# PollutagNode2_rev4_2026-10-08.net
KiCad netlist of a schematic drawn in EasyEDA Pro
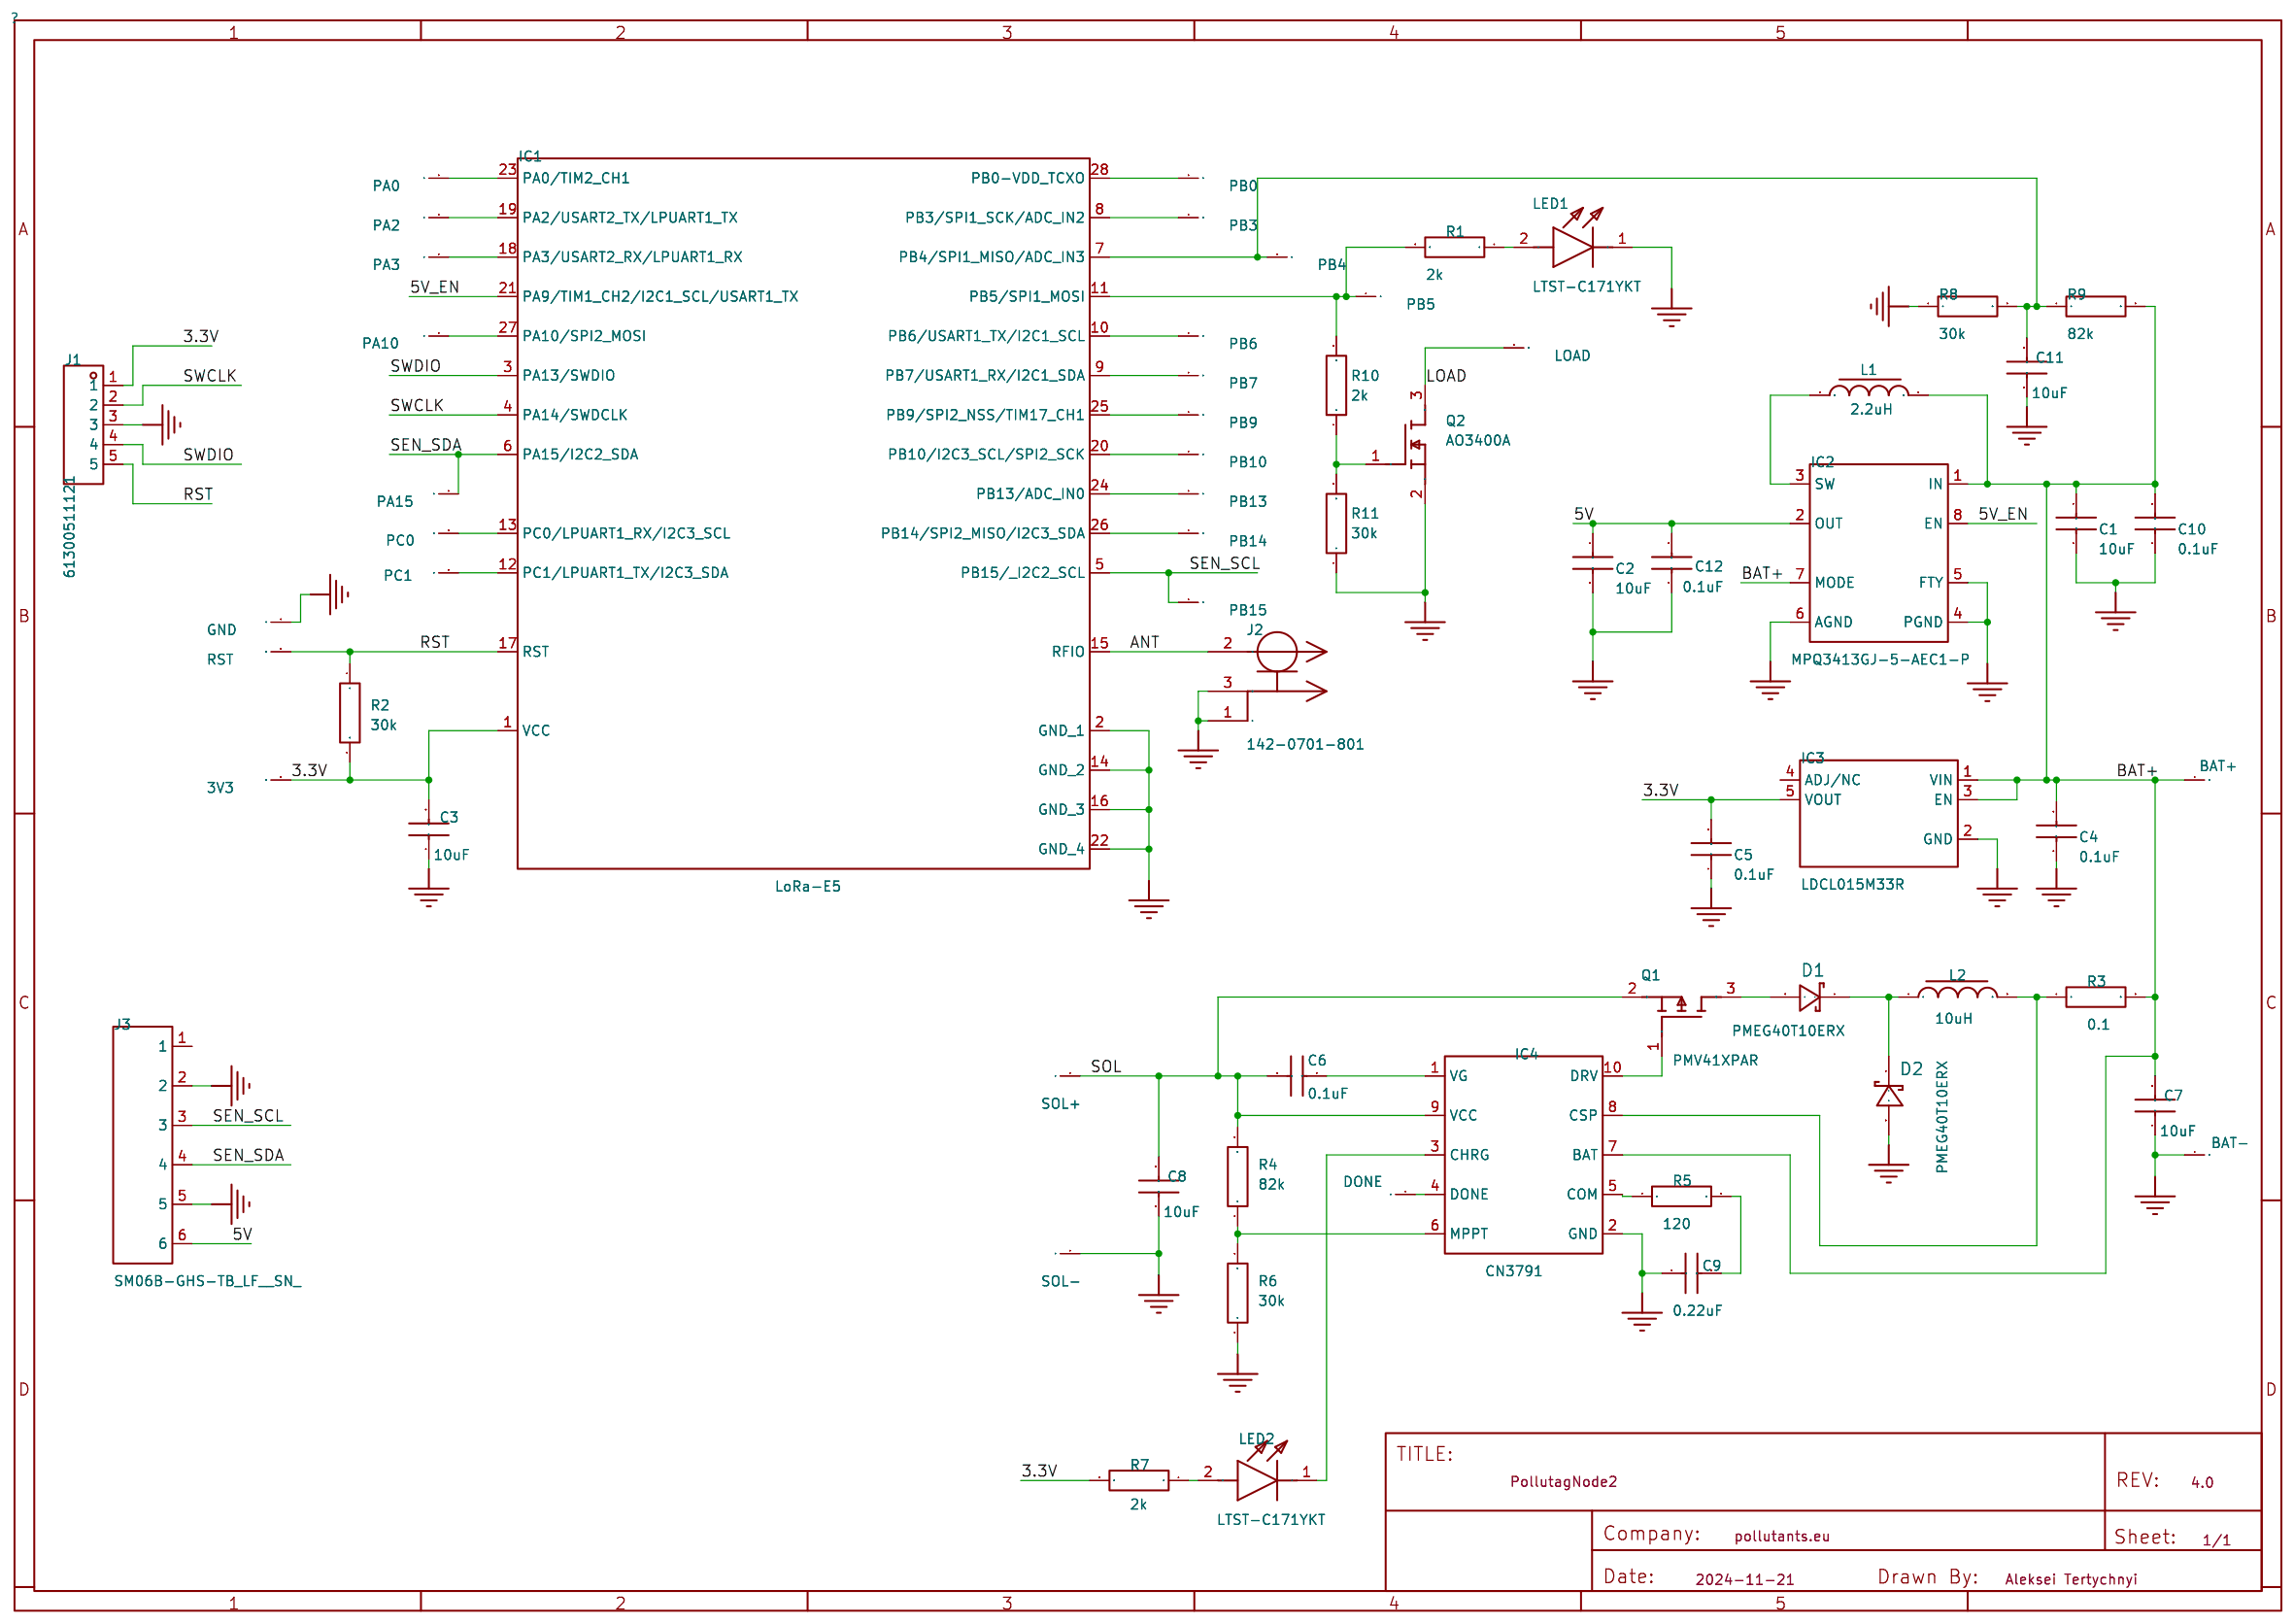
[diagram p0: schematic sheet]

(export (version "E")
  (design (tool "Eeschema 10.0.6"))
  (components
    (comp (ref "3V3")
      (value "S1751-46R")
      (fields (field (name "Manufacturer") "Harwin"))
      (libsource (lib "") (part "S1751-46R_1"))
    )
    (comp (ref "BAT+")
      (value "S1751-46R")
      (fields (field (name "Manufacturer") "Harwin"))
      (libsource (lib "easyedapro") (part "S1751-46R"))
    )
    (comp (ref "BAT-")
      (value "S1751-46R")
      (fields (field (name "Manufacturer") "Harwin"))
      (libsource (lib "easyedapro") (part "S1751-46R"))
    )
    (comp (ref "C1")
      (value "10uF")
      (fields
        (field (name "Manufacturer Part") "GRM188R61C106KALD")
        (field (name "Manufacturer") "Murata Electronics")
      )
      (libsource (lib "easyedapro") (part "10uF"))
    )
    (comp (ref "C2")
      (value "10uF")
      (fields
        (field (name "Manufacturer Part") "GRM188R61C106KALD")
        (field (name "Manufacturer") "Murata Electronics")
      )
      (libsource (lib "easyedapro") (part "10uF"))
    )
    (comp (ref "C3")
      (value "10uF")
      (fields
        (field (name "Manufacturer Part") "GRM188R61C106KALD")
        (field (name "Manufacturer") "Murata Electronics")
      )
      (libsource (lib "easyedapro") (part "10uF"))
    )
    (comp (ref "C4")
      (value "0.1uF")
      (fields (field (name "Manufacturer Part") "06035C104KAT2A") (field (name "Manufacturer") "AVX"))
      (libsource (lib "easyedapro") (part "0.1uF"))
    )
    (comp (ref "C5")
      (value "0.1uF")
      (fields (field (name "Manufacturer Part") "06035C104KAT2A") (field (name "Manufacturer") "AVX"))
      (libsource (lib "easyedapro") (part "0.1uF"))
    )
    (comp (ref "C6")
      (value "0.1uF")
      (fields (field (name "Manufacturer Part") "06035C104KAT2A") (field (name "Manufacturer") "AVX"))
      (libsource (lib "easyedapro") (part "0.1uF"))
    )
    (comp (ref "C7")
      (value "10uF")
      (fields
        (field (name "Manufacturer Part") "GRM188R61C106KALD")
        (field (name "Manufacturer") "Murata Electronics")
      )
      (libsource (lib "easyedapro") (part "10uF"))
    )
    (comp (ref "C8")
      (value "10uF")
      (fields
        (field (name "Manufacturer Part") "GRM188R61C106KALD")
        (field (name "Manufacturer") "Murata Electronics")
      )
      (libsource (lib "easyedapro") (part "10uF"))
    )
    (comp (ref "C9")
      (value "0.22uF")
      (fields (field (name "Manufacturer Part") "AC0603X7R9BB224") (field (name "Manufacturer") "KEMET"))
      (libsource (lib "easyedapro") (part "0.22uF"))
    )
    (comp (ref "C10")
      (value "0.1uF")
      (fields (field (name "Manufacturer Part") "06035C104KAT2A") (field (name "Manufacturer") "AVX"))
      (libsource (lib "easyedapro") (part "0.1uF"))
    )
    (comp (ref "C11")
      (value "10uF")
      (fields
        (field (name "Manufacturer Part") "GRM188R61C106KALD")
        (field (name "Manufacturer") "Murata Electronics")
      )
      (libsource (lib "easyedapro") (part "10uF"))
    )
    (comp (ref "C12")
      (value "0.1uF")
      (fields (field (name "Manufacturer Part") "06035C104KAT2A") (field (name "Manufacturer") "AVX"))
      (libsource (lib "easyedapro") (part "0.1uF"))
    )
    (comp (ref "D1")
      (value "PMEG40T10ERX")
      (footprint "easyedapro:SOD-123_L2.6-W1.7-LS3.5-RD")
      (fields (field (name "Manufacturer") "Nexperia(安世)"))
      (libsource (lib "easyedapro") (part "PMEG40T10ERX"))
    )
    (comp (ref "D2")
      (value "PMEG40T10ERX")
      (footprint "easyedapro:SOD-123_L2.6-W1.7-LS3.5-RD")
      (fields (field (name "Manufacturer") "Nexperia(安世)"))
      (libsource (lib "easyedapro") (part "PMEG40T10ERX"))
    )
    (comp (ref "DONE")
      (value "S1751-46R")
      (fields (field (name "Manufacturer") "Harwin"))
      (libsource (lib "") (part "S1751-46R_1"))
    )
    (comp (ref "GND")
      (value "S1751-46R")
      (fields (field (name "Manufacturer") "Harwin"))
      (libsource (lib "") (part "S1751-46R_1"))
    )
    (comp (ref "IC1")
      (value "LoRa-E5")
      (fields (field (name "Manufacturer Part") "317990687") (field (name "Manufacturer") "SEEED STUDIO"))
      (libsource (lib "easyedapro") (part "LoRa-E5"))
    )
    (comp (ref "IC2")
      (value "MPQ3413GJ-5-AEC1-P")
      (fields (field (name "Manufacturer") "Monolithic Power Systems (MPS)"))
      (libsource (lib "easyedapro") (part "MPQ3413GJ-5-AEC1-P"))
    )
    (comp (ref "IC3")
      (value "LDCL015M33R")
      (fields (field (name "Manufacturer") "STMicroelectronics"))
      (libsource (lib "easyedapro") (part "LDCL015M33R"))
    )
    (comp (ref "IC4")
      (value "CN3791")
      (fields (field (name "Manufacturer") "Consonance"))
      (libsource (lib "easyedapro") (part "CN3791"))
    )
    (comp (ref "J1")
      (value "61300511121")
      (footprint "easyedapro:HDR-TH_5P-P2.54-V-M")
      (fields (field (name "Manufacturer") "Wurth(伍尔特)"))
      (libsource (lib "easyedapro") (part "61300511121"))
    )
    (comp (ref "J2")
      (value "142-0701-801")
      (fields (field (name "Manufacturer") "Cinch Connectivity Solutions"))
      (libsource (lib "easyedapro") (part "142-0701-801"))
    )
    (comp (ref "J3")
      (value "SM06B-GHS-TB_LF__SN_")
      (fields
        (field (name "Manufacturer Part") "SM06B-GHS-TB(LF)(SN)")
        (field (name "Manufacturer") "JST (JAPAN SOLDERLESS TERMINALS)")
      )
      (libsource (lib "easyedapro") (part "SM06B-GHS-TB_LF__SN_"))
    )
    (comp (ref "L1")
      (value "2.2uH")
      (fields (field (name "Manufacturer Part") "SRN3015-2R2M") (field (name "Manufacturer") "Bourns"))
      (libsource (lib "easyedapro") (part "2.2uH"))
    )
    (comp (ref "L2")
      (value "10uH")
      (fields (field (name "Manufacturer Part") "SRN3015BTA-100M") (field (name "Manufacturer") "Bourns"))
      (libsource (lib "easyedapro") (part "10uH"))
    )
    (comp (ref "LED1")
      (value "LTST-C171YKT")
      (fields (field (name "Manufacturer") "Lite-On"))
      (libsource (lib "easyedapro") (part "LTST-C171YKT"))
    )
    (comp (ref "LED2")
      (value "LTST-C171YKT")
      (fields (field (name "Manufacturer") "Lite-On"))
      (libsource (lib "easyedapro") (part "LTST-C171YKT"))
    )
    (comp (ref "LOAD")
      (value "S1751-46R")
      (fields (field (name "Manufacturer") "Harwin"))
      (libsource (lib "easyedapro") (part "S1751-46R"))
    )
    (comp (ref "PA0")
      (value "S1751-46R")
      (fields (field (name "Manufacturer") "Harwin"))
      (libsource (lib "") (part "S1751-46R_1"))
    )
    (comp (ref "PA2")
      (value "S1751-46R")
      (fields (field (name "Manufacturer") "Harwin"))
      (libsource (lib "") (part "S1751-46R_1"))
    )
    (comp (ref "PA3")
      (value "S1751-46R")
      (fields (field (name "Manufacturer") "Harwin"))
      (libsource (lib "") (part "S1751-46R_1"))
    )
    (comp (ref "PA10")
      (value "S1751-46R")
      (fields (field (name "Manufacturer") "Harwin"))
      (libsource (lib "") (part "S1751-46R_1"))
    )
    (comp (ref "PA15")
      (value "S1751-46R")
      (fields (field (name "Manufacturer") "Harwin"))
      (libsource (lib "") (part "S1751-46R_1"))
    )
    (comp (ref "PB0")
      (value "S1751-46R")
      (fields (field (name "Manufacturer") "Harwin"))
      (libsource (lib "easyedapro") (part "S1751-46R"))
    )
    (comp (ref "PB3")
      (value "S1751-46R")
      (fields (field (name "Manufacturer") "Harwin"))
      (libsource (lib "easyedapro") (part "S1751-46R"))
    )
    (comp (ref "PB4")
      (value "S1751-46R")
      (fields (field (name "Manufacturer") "Harwin"))
      (libsource (lib "easyedapro") (part "S1751-46R"))
    )
    (comp (ref "PB5")
      (value "S1751-46R")
      (fields (field (name "Manufacturer") "Harwin"))
      (libsource (lib "easyedapro") (part "S1751-46R"))
    )
    (comp (ref "PB6")
      (value "S1751-46R")
      (fields (field (name "Manufacturer") "Harwin"))
      (libsource (lib "easyedapro") (part "S1751-46R"))
    )
    (comp (ref "PB7")
      (value "S1751-46R")
      (fields (field (name "Manufacturer") "Harwin"))
      (libsource (lib "easyedapro") (part "S1751-46R"))
    )
    (comp (ref "PB9")
      (value "S1751-46R")
      (fields (field (name "Manufacturer") "Harwin"))
      (libsource (lib "easyedapro") (part "S1751-46R"))
    )
    (comp (ref "PB10")
      (value "S1751-46R")
      (fields (field (name "Manufacturer") "Harwin"))
      (libsource (lib "easyedapro") (part "S1751-46R"))
    )
    (comp (ref "PB13")
      (value "S1751-46R")
      (fields (field (name "Manufacturer") "Harwin"))
      (libsource (lib "easyedapro") (part "S1751-46R"))
    )
    (comp (ref "PB14")
      (value "S1751-46R")
      (fields (field (name "Manufacturer") "Harwin"))
      (libsource (lib "easyedapro") (part "S1751-46R"))
    )
    (comp (ref "PB15")
      (value "S1751-46R")
      (fields (field (name "Manufacturer") "Harwin"))
      (libsource (lib "easyedapro") (part "S1751-46R"))
    )
    (comp (ref "PC0")
      (value "S1751-46R")
      (fields (field (name "Manufacturer") "Harwin"))
      (libsource (lib "") (part "S1751-46R_1"))
    )
    (comp (ref "PC1")
      (value "S1751-46R")
      (fields (field (name "Manufacturer") "Harwin"))
      (libsource (lib "") (part "S1751-46R_1"))
    )
    (comp (ref "Q1")
      (value "PMV41XPAR")
      (fields (field (name "Manufacturer") "Nexperia"))
      (libsource (lib "easyedapro") (part "PMV41XPAR"))
    )
    (comp (ref "Q2")
      (value "AO3400A")
      (fields (field (name "Manufacturer") "Alpha & Omega Semiconductors"))
      (libsource (lib "easyedapro") (part "AO3400A"))
    )
    (comp (ref "R1")
      (value "2k")
      (fields (field (name "Manufacturer Part") "RC0603FR-072KL") (field (name "Manufacturer") "Yageo"))
      (libsource (lib "easyedapro") (part "2k"))
    )
    (comp (ref "R2")
      (value "30k")
      (fields (field (name "Manufacturer Part") "CR0603-FX-3002ELF") (field (name "Manufacturer") "Bourns"))
      (libsource (lib "easyedapro") (part "30k"))
    )
    (comp (ref "R3")
      (value "0.1")
      (fields (field (name "Manufacturer Part") "CRL1206FWR100ELF") (field (name "Manufacturer") "Bourns"))
      (libsource (lib "easyedapro") (part "0.1"))
    )
    (comp (ref "R4")
      (value "82k")
      (fields (field (name "Manufacturer Part") "RT0603FRE0782KL") (field (name "Manufacturer") "KEMET"))
      (libsource (lib "easyedapro") (part "82k"))
    )
    (comp (ref "R5")
      (value "120")
      (fields (field (name "Manufacturer Part") "ERJ-U03J121V") (field (name "Manufacturer") "Panasonic"))
      (libsource (lib "easyedapro") (part "120"))
    )
    (comp (ref "R6")
      (value "30k")
      (fields (field (name "Manufacturer Part") "CR0603-FX-3002ELF") (field (name "Manufacturer") "Bourns"))
      (libsource (lib "easyedapro") (part "30k"))
    )
    (comp (ref "R7")
      (value "2k")
      (fields (field (name "Manufacturer Part") "RC0603FR-072KL") (field (name "Manufacturer") "Yageo"))
      (libsource (lib "easyedapro") (part "2k"))
    )
    (comp (ref "R8")
      (value "30k")
      (fields (field (name "Manufacturer Part") "CR0603-FX-3002ELF") (field (name "Manufacturer") "Bourns"))
      (libsource (lib "easyedapro") (part "30k"))
    )
    (comp (ref "R9")
      (value "82k")
      (fields (field (name "Manufacturer Part") "RT0603FRE0782KL") (field (name "Manufacturer") "KEMET"))
      (libsource (lib "easyedapro") (part "82k"))
    )
    (comp (ref "R10")
      (value "2k")
      (fields (field (name "Manufacturer Part") "RC0603FR-072KL") (field (name "Manufacturer") "Yageo"))
      (libsource (lib "easyedapro") (part "2k"))
    )
    (comp (ref "R11")
      (value "30k")
      (fields (field (name "Manufacturer Part") "CR0603-FX-3002ELF") (field (name "Manufacturer") "Bourns"))
      (libsource (lib "easyedapro") (part "30k"))
    )
    (comp (ref "RST")
      (value "S1751-46R")
      (fields (field (name "Manufacturer") "Harwin"))
      (libsource (lib "") (part "S1751-46R_1"))
    )
    (comp (ref "SOL+")
      (value "S1751-46R")
      (fields (field (name "Manufacturer") "Harwin"))
      (libsource (lib "") (part "S1751-46R_1"))
    )
    (comp (ref "SOL-")
      (value "S1751-46R")
      (fields (field (name "Manufacturer") "Harwin"))
      (libsource (lib "") (part "S1751-46R_1"))
    )
  )
  (nets
    (net (code "1") (name "/3.3V") (class "Default")
      (node (ref "3V3") (pin "1") (pinfunction "1_1") (pintype "unspecified"))
      (node (ref "C3") (pin "2") (pinfunction "2_2") (pintype "unspecified"))
      (node (ref "C5") (pin "2") (pinfunction "2_2") (pintype "unspecified"))
      (node (ref "IC1") (pin "1") (pinfunction "VCC_1") (pintype "unspecified"))
      (node (ref "IC3") (pin "5") (pinfunction "VOUT_5") (pintype "unspecified"))
      (node (ref "J1") (pin "1") (pinfunction "1_1") (pintype "unspecified"))
      (node (ref "R2") (pin "2") (pinfunction "2_2") (pintype "unspecified"))
      (node (ref "R7") (pin "2") (pinfunction "2_2") (pintype "unspecified"))
    )
    (net (code "2") (name "/5V") (class "Default")
      (node (ref "C12") (pin "2") (pinfunction "2_2") (pintype "unspecified"))
      (node (ref "C2") (pin "1") (pinfunction "1_1") (pintype "unspecified"))
      (node (ref "IC2") (pin "2") (pinfunction "OUT_2") (pintype "unspecified"))
      (node (ref "J3") (pin "6") (pinfunction "6_6") (pintype "unspecified"))
    )
    (net (code "3") (name "/5V_EN") (class "Default")
      (node (ref "IC1") (pin "21") (pinfunction "PA9/TIM1_CH2/I2C1_SCL/USART1_TX_21") (pintype "unspecified"))
      (node (ref "IC2") (pin "8") (pinfunction "EN_8") (pintype "unspecified"))
    )
    (net (code "4") (name "/ANT") (class "Default")
      (node (ref "IC1") (pin "15") (pinfunction "RFIO_15") (pintype "unspecified"))
      (node (ref "J2") (pin "2") (pinfunction "2_2") (pintype "unspecified"))
    )
    (net (code "5") (name "/BAT+") (class "Default")
      (node (ref "BAT+") (pin "1") (pinfunction "1_1") (pintype "unspecified"))
      (node (ref "C1") (pin "1") (pinfunction "1_1") (pintype "unspecified"))
      (node (ref "C10") (pin "2") (pinfunction "2_2") (pintype "unspecified"))
      (node (ref "C4") (pin "2") (pinfunction "2_2") (pintype "unspecified"))
      (node (ref "C7") (pin "2") (pinfunction "2_2") (pintype "unspecified"))
      (node (ref "IC2") (pin "1") (pinfunction "IN_1") (pintype "unspecified"))
      (node (ref "IC2") (pin "7") (pinfunction "MODE_7") (pintype "unspecified"))
      (node (ref "IC3") (pin "1") (pinfunction "VIN_1") (pintype "unspecified"))
      (node (ref "IC3") (pin "3") (pinfunction "EN_3") (pintype "unspecified"))
      (node (ref "IC4") (pin "7") (pinfunction "BAT_7") (pintype "unspecified"))
      (node (ref "L1") (pin "1") (pinfunction "1_1") (pintype "unspecified"))
      (node (ref "R3") (pin "2") (pinfunction "2_2") (pintype "unspecified"))
      (node (ref "R9") (pin "2") (pinfunction "2_2") (pintype "unspecified"))
    )
    (net (code "6") (name "/LOAD") (class "Default")
      (node (ref "LOAD") (pin "1") (pinfunction "1_1") (pintype "unspecified"))
      (node (ref "Q2") (pin "3") (pinfunction "D_3") (pintype "unspecified"))
    )
    (net (code "7") (name "/RST") (class "Default")
      (node (ref "IC1") (pin "17") (pinfunction "RST_17") (pintype "unspecified"))
      (node (ref "J1") (pin "5") (pinfunction "5_5") (pintype "unspecified"))
      (node (ref "R2") (pin "1") (pinfunction "1_1") (pintype "unspecified"))
      (node (ref "RST") (pin "1") (pinfunction "1_1") (pintype "unspecified"))
    )
    (net (code "8") (name "/SEN_SCL") (class "Default")
      (node (ref "IC1") (pin "5") (pinfunction "PB15/_I2C2_SCL_5") (pintype "unspecified"))
      (node (ref "J3") (pin "3") (pinfunction "3_3") (pintype "unspecified"))
      (node (ref "PB15") (pin "1") (pinfunction "1_1") (pintype "unspecified"))
    )
    (net (code "9") (name "/SEN_SDA") (class "Default")
      (node (ref "IC1") (pin "6") (pinfunction "PA15/I2C2_SDA_6") (pintype "unspecified"))
      (node (ref "J3") (pin "4") (pinfunction "4_4") (pintype "unspecified"))
      (node (ref "PA15") (pin "1") (pinfunction "1_1") (pintype "unspecified"))
    )
    (net (code "10") (name "/SOL") (class "Default")
      (node (ref "C6") (pin "1") (pinfunction "1_1") (pintype "unspecified"))
      (node (ref "C8") (pin "2") (pinfunction "2_2") (pintype "unspecified"))
      (node (ref "IC4") (pin "9") (pinfunction "VCC_9") (pintype "unspecified"))
      (node (ref "Q1") (pin "2") (pinfunction "S_2") (pintype "unspecified"))
      (node (ref "R4") (pin "2") (pinfunction "2_2") (pintype "unspecified"))
      (node (ref "SOL+") (pin "1") (pinfunction "1_1") (pintype "unspecified"))
    )
    (net (code "11") (name "/SWCLK") (class "Default")
      (node (ref "IC1") (pin "4") (pinfunction "PA14/SWDCLK_4") (pintype "unspecified"))
      (node (ref "J1") (pin "2") (pinfunction "2_2") (pintype "unspecified"))
    )
    (net (code "12") (name "/SWDIO") (class "Default")
      (node (ref "IC1") (pin "3") (pinfunction "PA13/SWDIO_3") (pintype "unspecified"))
      (node (ref "J1") (pin "4") (pinfunction "4_4") (pintype "unspecified"))
    )
    (net (code "13") (name "GND") (class "Default")
      (node (ref "BAT-") (pin "1") (pinfunction "1_1") (pintype "unspecified"))
      (node (ref "C1") (pin "2") (pinfunction "2_2") (pintype "unspecified"))
      (node (ref "C10") (pin "1") (pinfunction "1_1") (pintype "unspecified"))
      (node (ref "C11") (pin "1") (pinfunction "1_1") (pintype "unspecified"))
      (node (ref "C12") (pin "1") (pinfunction "1_1") (pintype "unspecified"))
      (node (ref "C2") (pin "2") (pinfunction "2_2") (pintype "unspecified"))
      (node (ref "C3") (pin "1") (pinfunction "1_1") (pintype "unspecified"))
      (node (ref "C4") (pin "1") (pinfunction "1_1") (pintype "unspecified"))
      (node (ref "C5") (pin "1") (pinfunction "1_1") (pintype "unspecified"))
      (node (ref "C7") (pin "1") (pinfunction "1_1") (pintype "unspecified"))
      (node (ref "C8") (pin "1") (pinfunction "1_1") (pintype "unspecified"))
      (node (ref "C9") (pin "1") (pinfunction "1_1") (pintype "unspecified"))
      (node (ref "D2") (pin "2") (pinfunction "+_2") (pintype "input"))
      (node (ref "GND") (pin "1") (pinfunction "1_1") (pintype "unspecified"))
      (node (ref "IC1") (pin "14") (pinfunction "GND_2_14") (pintype "unspecified"))
      (node (ref "IC1") (pin "16") (pinfunction "GND_3_16") (pintype "unspecified"))
      (node (ref "IC1") (pin "2") (pinfunction "GND_1_2") (pintype "unspecified"))
      (node (ref "IC1") (pin "22") (pinfunction "GND_4_22") (pintype "unspecified"))
      (node (ref "IC2") (pin "4") (pinfunction "PGND_4") (pintype "unspecified"))
      (node (ref "IC2") (pin "5") (pinfunction "FTY_5") (pintype "unspecified"))
      (node (ref "IC2") (pin "6") (pinfunction "AGND_6") (pintype "unspecified"))
      (node (ref "IC3") (pin "2") (pinfunction "GND_2") (pintype "unspecified"))
      (node (ref "IC4") (pin "2") (pinfunction "GND_2") (pintype "unspecified"))
      (node (ref "J1") (pin "3") (pinfunction "3_3") (pintype "unspecified"))
      (node (ref "J2") (pin "1") (pinfunction "1_1") (pintype "unspecified"))
      (node (ref "J2") (pin "3") (pinfunction "3_3") (pintype "unspecified"))
      (node (ref "J3") (pin "2") (pinfunction "2_2") (pintype "unspecified"))
      (node (ref "J3") (pin "5") (pinfunction "5_5") (pintype "unspecified"))
      (node (ref "LED1") (pin "1") (pinfunction "K_1") (pintype "unspecified"))
      (node (ref "Q2") (pin "2") (pinfunction "S_2") (pintype "unspecified"))
      (node (ref "R11") (pin "1") (pinfunction "1_1") (pintype "unspecified"))
      (node (ref "R6") (pin "1") (pinfunction "1_1") (pintype "unspecified"))
      (node (ref "R8") (pin "1") (pinfunction "1_1") (pintype "unspecified"))
      (node (ref "SOL-") (pin "1") (pinfunction "1_1") (pintype "unspecified"))
    )
    (net (code "14") (name "Net-(C9-Pad2)") (class "Default")
      (node (ref "C9") (pin "2") (pinfunction "2_2") (pintype "unspecified"))
      (node (ref "R5") (pin "2") (pinfunction "2_2") (pintype "unspecified"))
    )
    (net (code "15") (name "Net-(D1-+)") (class "Default")
      (node (ref "D1") (pin "2") (pinfunction "+_2") (pintype "input"))
      (node (ref "Q1") (pin "3") (pinfunction "D_3") (pintype "unspecified"))
    )
    (net (code "16") (name "Net-(D1--)") (class "Default")
      (node (ref "D1") (pin "1") (pinfunction "-_1") (pintype "input"))
      (node (ref "D2") (pin "1") (pinfunction "-_1") (pintype "input"))
      (node (ref "L2") (pin "1") (pinfunction "1_1") (pintype "unspecified"))
    )
    (net (code "17") (name "Net-(IC1-PA0{slash}TIM2_CH1)") (class "Default")
      (node (ref "IC1") (pin "23") (pinfunction "PA0/TIM2_CH1_23") (pintype "unspecified"))
      (node (ref "PA0") (pin "1") (pinfunction "1_1") (pintype "unspecified"))
    )
    (net (code "18") (name "Net-(IC1-PA2{slash}USART2_TX{slash}LPUART1_TX)") (class "Default")
      (node (ref "IC1") (pin "19") (pinfunction "PA2/USART2_TX/LPUART1_TX_19") (pintype "unspecified"))
      (node (ref "PA2") (pin "1") (pinfunction "1_1") (pintype "unspecified"))
    )
    (net (code "19") (name "Net-(IC1-PA3{slash}USART2_RX{slash}LPUART1_RX)") (class "Default")
      (node (ref "IC1") (pin "18") (pinfunction "PA3/USART2_RX/LPUART1_RX_18") (pintype "unspecified"))
      (node (ref "PA3") (pin "1") (pinfunction "1_1") (pintype "unspecified"))
    )
    (net (code "20") (name "Net-(IC1-PA10{slash}SPI2_MOSI)") (class "Default")
      (node (ref "IC1") (pin "27") (pinfunction "PA10/SPI2_MOSI_27") (pintype "unspecified"))
      (node (ref "PA10") (pin "1") (pinfunction "1_1") (pintype "unspecified"))
    )
    (net (code "21") (name "Net-(IC1-PB0-VDD_TCXO)") (class "Default")
      (node (ref "IC1") (pin "28") (pinfunction "PB0-VDD_TCXO_28") (pintype "unspecified"))
      (node (ref "PB0") (pin "1") (pinfunction "1_1") (pintype "unspecified"))
    )
    (net (code "22") (name "Net-(IC1-PB3{slash}SPI1_SCK{slash}ADC_IN2)") (class "Default")
      (node (ref "IC1") (pin "8") (pinfunction "PB3/SPI1_SCK/ADC_IN2_8") (pintype "unspecified"))
      (node (ref "PB3") (pin "1") (pinfunction "1_1") (pintype "unspecified"))
    )
    (net (code "23") (name "Net-(IC1-PB4{slash}SPI1_MISO{slash}ADC_IN3)") (class "Default")
      (node (ref "C11") (pin "2") (pinfunction "2_2") (pintype "unspecified"))
      (node (ref "IC1") (pin "7") (pinfunction "PB4/SPI1_MISO/ADC_IN3_7") (pintype "unspecified"))
      (node (ref "PB4") (pin "1") (pinfunction "1_1") (pintype "unspecified"))
      (node (ref "R8") (pin "2") (pinfunction "2_2") (pintype "unspecified"))
      (node (ref "R9") (pin "1") (pinfunction "1_1") (pintype "unspecified"))
    )
    (net (code "24") (name "Net-(IC1-PB5{slash}SPI1_MOSI)") (class "Default")
      (node (ref "IC1") (pin "11") (pinfunction "PB5/SPI1_MOSI_11") (pintype "unspecified"))
      (node (ref "PB5") (pin "1") (pinfunction "1_1") (pintype "unspecified"))
      (node (ref "R1") (pin "2") (pinfunction "2_2") (pintype "unspecified"))
      (node (ref "R10") (pin "2") (pinfunction "2_2") (pintype "unspecified"))
    )
    (net (code "25") (name "Net-(IC1-PB6{slash}USART1_TX{slash}I2C1_SCL)") (class "Default")
      (node (ref "IC1") (pin "10") (pinfunction "PB6/USART1_TX/I2C1_SCL_10") (pintype "unspecified"))
      (node (ref "PB6") (pin "1") (pinfunction "1_1") (pintype "unspecified"))
    )
    (net (code "26") (name "Net-(IC1-PB7{slash}USART1_RX{slash}I2C1_SDA)") (class "Default")
      (node (ref "IC1") (pin "9") (pinfunction "PB7/USART1_RX/I2C1_SDA_9") (pintype "unspecified"))
      (node (ref "PB7") (pin "1") (pinfunction "1_1") (pintype "unspecified"))
    )
    (net (code "27") (name "Net-(IC1-PB9{slash}SPI2_NSS{slash}TIM17_CH1)") (class "Default")
      (node (ref "IC1") (pin "25") (pinfunction "PB9/SPI2_NSS/TIM17_CH1_25") (pintype "unspecified"))
      (node (ref "PB9") (pin "1") (pinfunction "1_1") (pintype "unspecified"))
    )
    (net (code "28") (name "Net-(IC1-PB10{slash}I2C3_SCL{slash}SPI2_SCK)") (class "Default")
      (node (ref "IC1") (pin "20") (pinfunction "PB10/I2C3_SCL/SPI2_SCK_20") (pintype "unspecified"))
      (node (ref "PB10") (pin "1") (pinfunction "1_1") (pintype "unspecified"))
    )
    (net (code "29") (name "Net-(IC1-PB13{slash}ADC_IN0)") (class "Default")
      (node (ref "IC1") (pin "24") (pinfunction "PB13/ADC_IN0_24") (pintype "unspecified"))
      (node (ref "PB13") (pin "1") (pinfunction "1_1") (pintype "unspecified"))
    )
    (net (code "30") (name "Net-(IC1-PB14{slash}SPI2_MISO{slash}I2C3_SDA)") (class "Default")
      (node (ref "IC1") (pin "26") (pinfunction "PB14/SPI2_MISO/I2C3_SDA_26") (pintype "unspecified"))
      (node (ref "PB14") (pin "1") (pinfunction "1_1") (pintype "unspecified"))
    )
    (net (code "31") (name "Net-(IC1-PC0{slash}LPUART1_RX{slash}I2C3_SCL)") (class "Default")
      (node (ref "IC1") (pin "13") (pinfunction "PC0/LPUART1_RX/I2C3_SCL_13") (pintype "unspecified"))
      (node (ref "PC0") (pin "1") (pinfunction "1_1") (pintype "unspecified"))
    )
    (net (code "32") (name "Net-(IC1-PC1{slash}LPUART1_TX{slash}I2C3_SDA)") (class "Default")
      (node (ref "IC1") (pin "12") (pinfunction "PC1/LPUART1_TX/I2C3_SDA_12") (pintype "unspecified"))
      (node (ref "PC1") (pin "1") (pinfunction "1_1") (pintype "unspecified"))
    )
    (net (code "33") (name "Net-(IC2-SW)") (class "Default")
      (node (ref "IC2") (pin "3") (pinfunction "SW_3") (pintype "unspecified"))
      (node (ref "L1") (pin "2") (pinfunction "2_2") (pintype "unspecified"))
    )
    (net (code "34") (name "Net-(IC4-CHRG)") (class "Default")
      (node (ref "IC4") (pin "3") (pinfunction "CHRG_3") (pintype "unspecified"))
      (node (ref "LED2") (pin "1") (pinfunction "K_1") (pintype "unspecified"))
    )
    (net (code "35") (name "Net-(IC4-COM)") (class "Default")
      (node (ref "IC4") (pin "5") (pinfunction "COM_5") (pintype "unspecified"))
      (node (ref "R5") (pin "1") (pinfunction "1_1") (pintype "unspecified"))
    )
    (net (code "36") (name "Net-(IC4-CSP)") (class "Default")
      (node (ref "IC4") (pin "8") (pinfunction "CSP_8") (pintype "unspecified"))
      (node (ref "L2") (pin "2") (pinfunction "2_2") (pintype "unspecified"))
      (node (ref "R3") (pin "1") (pinfunction "1_1") (pintype "unspecified"))
    )
    (net (code "37") (name "Net-(IC4-DONE)") (class "Default")
      (node (ref "DONE") (pin "1") (pinfunction "1_1") (pintype "unspecified"))
      (node (ref "IC4") (pin "4") (pinfunction "DONE_4") (pintype "unspecified"))
    )
    (net (code "38") (name "Net-(IC4-DRV)") (class "Default")
      (node (ref "IC4") (pin "10") (pinfunction "DRV_10") (pintype "unspecified"))
      (node (ref "Q1") (pin "1") (pinfunction "G_1") (pintype "unspecified"))
    )
    (net (code "39") (name "Net-(IC4-MPPT)") (class "Default")
      (node (ref "IC4") (pin "6") (pinfunction "MPPT_6") (pintype "unspecified"))
      (node (ref "R4") (pin "1") (pinfunction "1_1") (pintype "unspecified"))
      (node (ref "R6") (pin "2") (pinfunction "2_2") (pintype "unspecified"))
    )
    (net (code "40") (name "Net-(IC4-VG)") (class "Default")
      (node (ref "C6") (pin "2") (pinfunction "2_2") (pintype "unspecified"))
      (node (ref "IC4") (pin "1") (pinfunction "VG_1") (pintype "unspecified"))
    )
    (net (code "41") (name "Net-(LED1-A)") (class "Default")
      (node (ref "LED1") (pin "2") (pinfunction "A_2") (pintype "unspecified"))
      (node (ref "R1") (pin "1") (pinfunction "1_1") (pintype "unspecified"))
    )
    (net (code "42") (name "Net-(LED2-A)") (class "Default")
      (node (ref "LED2") (pin "2") (pinfunction "A_2") (pintype "unspecified"))
      (node (ref "R7") (pin "1") (pinfunction "1_1") (pintype "unspecified"))
    )
    (net (code "43") (name "Net-(Q2-G)") (class "Default")
      (node (ref "Q2") (pin "1") (pinfunction "G_1") (pintype "unspecified"))
      (node (ref "R10") (pin "1") (pinfunction "1_1") (pintype "unspecified"))
      (node (ref "R11") (pin "2") (pinfunction "2_2") (pintype "unspecified"))
    )
    (net (code "44") (name "unconnected-(IC3-ADJ{slash}NC-Pad4)") (class "Default")
      (node (ref "IC3") (pin "4") (pinfunction "ADJ/NC_4") (pintype "unspecified"))
    )
    (net (code "45") (name "unconnected-(J3-Pad1)") (class "Default")
      (node (ref "J3") (pin "1") (pinfunction "1_1") (pintype "unspecified"))
    )
  )
)
